# 8eye_line_sensor.net
KiCad netlist of a schematic drawn in EAGLE
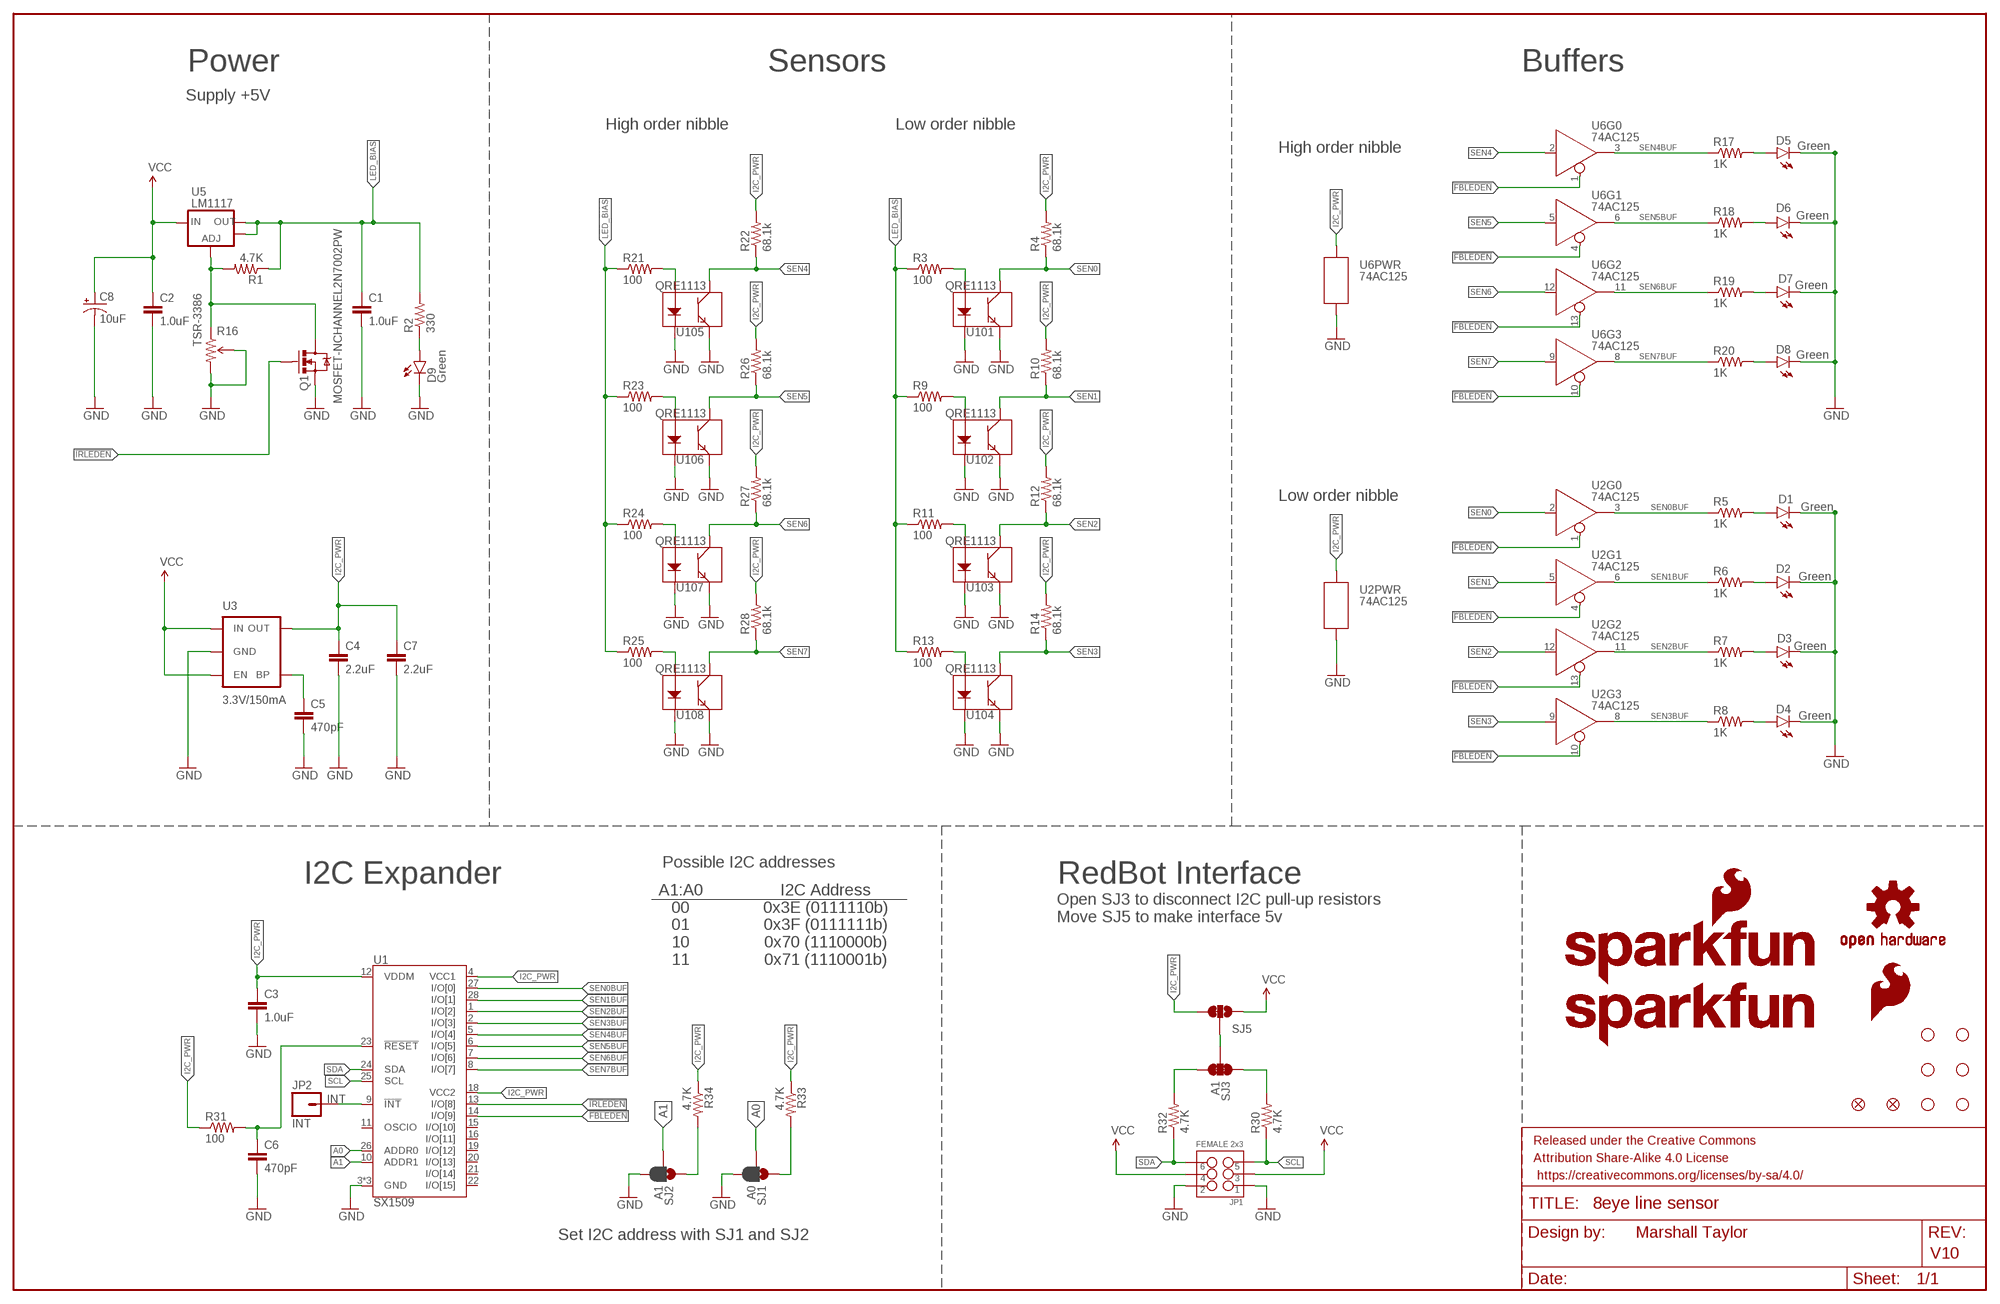
[diagram p0: schematic, sheet 1]

(export (version "E")
  (design (tool "Eeschema 10.0.6"))
  (components
    (comp (ref "C1")
      (value "1.0uF")
      (footprint "eagle-import:0603-CAP")
      (libsource (lib "eagle-import") (part "1.0UF-16V-10%(0603)"))
    )
    (comp (ref "C2")
      (value "1.0uF")
      (footprint "eagle-import:0603-CAP")
      (libsource (lib "eagle-import") (part "1.0UF-16V-10%(0603)"))
    )
    (comp (ref "C3")
      (value "1.0uF")
      (footprint "eagle-import:0603-CAP")
      (libsource (lib "eagle-import") (part "1.0UF-16V-10%(0603)"))
    )
    (comp (ref "C4")
      (value "2.2uF")
      (footprint "eagle-import:0603-CAP")
      (libsource (lib "eagle-import") (part "2.2UF-10V-20%(0603)"))
    )
    (comp (ref "C5")
      (value "470pF")
      (footprint "eagle-import:0603-CAP")
      (libsource (lib "eagle-import") (part "470PF-50V-5%(0603)SMD"))
    )
    (comp (ref "C6")
      (value "470pF")
      (footprint "eagle-import:0603-CAP")
      (libsource (lib "eagle-import") (part "470PF-50V-5%(0603)SMD"))
    )
    (comp (ref "C7")
      (value "2.2uF")
      (footprint "eagle-import:0603-CAP")
      (libsource (lib "eagle-import") (part "2.2UF-10V-20%(0603)"))
    )
    (comp (ref "C8")
      (value "10uF")
      (footprint "eagle-import:EIA3216")
      (libsource (lib "eagle-import") (part "10UF-16V-10%(TANT)"))
    )
    (comp (ref "D1")
      (value "Green")
      (footprint "eagle-import:LED-1206-BOTTOM")
      (libsource (lib "eagle-import") (part "LED-GREEN1206-BOTTOM"))
    )
    (comp (ref "D2")
      (value "Green")
      (footprint "eagle-import:LED-1206-BOTTOM")
      (libsource (lib "eagle-import") (part "LED-GREEN1206-BOTTOM"))
    )
    (comp (ref "D3")
      (value "Green")
      (footprint "eagle-import:LED-1206-BOTTOM")
      (libsource (lib "eagle-import") (part "LED-GREEN1206-BOTTOM"))
    )
    (comp (ref "D4")
      (value "Green")
      (footprint "eagle-import:LED-1206-BOTTOM")
      (libsource (lib "eagle-import") (part "LED-GREEN1206-BOTTOM"))
    )
    (comp (ref "D5")
      (value "Green")
      (footprint "eagle-import:LED-1206-BOTTOM")
      (libsource (lib "eagle-import") (part "LED-GREEN1206-BOTTOM"))
    )
    (comp (ref "D6")
      (value "Green")
      (footprint "eagle-import:LED-1206-BOTTOM")
      (libsource (lib "eagle-import") (part "LED-GREEN1206-BOTTOM"))
    )
    (comp (ref "D7")
      (value "Green")
      (footprint "eagle-import:LED-1206-BOTTOM")
      (libsource (lib "eagle-import") (part "LED-GREEN1206-BOTTOM"))
    )
    (comp (ref "D8")
      (value "Green")
      (footprint "eagle-import:LED-1206-BOTTOM")
      (libsource (lib "eagle-import") (part "LED-GREEN1206-BOTTOM"))
    )
    (comp (ref "D9")
      (value "Green")
      (footprint "eagle-import:LED-1206-BOTTOM")
      (libsource (lib "eagle-import") (part "LED-GREEN1206-BOTTOM"))
    )
    (comp (ref "FID1")
      (value "FIDUCIALUFIDUCIAL")
      (footprint "eagle-import:MICRO-FIDUCIAL")
      (libsource (lib "eagle-import") (part "FIDUCIALUFIDUCIAL"))
    )
    (comp (ref "FID2")
      (value "FIDUCIALUFIDUCIAL")
      (footprint "eagle-import:MICRO-FIDUCIAL")
      (libsource (lib "eagle-import") (part "FIDUCIALUFIDUCIAL"))
    )
    (comp (ref "FRAME2")
      (value "FRAME-LEDGER")
      (footprint "eagle-import:CREATIVE_COMMONS")
      (libsource (lib "eagle-import") (part "FRAME-LEDGER"))
    )
    (comp (ref "JP1")
      (value "FEMALE 2x3")
      (footprint "eagle-import:2X3")
      (libsource (lib "eagle-import") (part "M03X2FEMALE"))
    )
    (comp (ref "JP2")
      (value "INT")
      (footprint "eagle-import:1X01")
      (libsource (lib "eagle-import") (part "M01PTH"))
    )
    (comp (ref "LOGO1")
      (value "SFE_LOGO_NAME_FLAME.2_INCH")
      (footprint "eagle-import:SFE_LOGO_NAME_FLAME_.2")
      (libsource (lib "eagle-import") (part "SFE_LOGO_NAME_FLAME.2_INCH"))
    )
    (comp (ref "LOGO2")
      (value "SFE_LOGO_NAME.2_INCH")
      (footprint "eagle-import:SFE_LOGO_NAME_.2")
      (libsource (lib "eagle-import") (part "SFE_LOGO_NAME.2_INCH"))
    )
    (comp (ref "LOGO5")
      (value "SFE_LOGO_FLAME.3_INCH")
      (footprint "eagle-import:SFE_LOGO_FLAME_.3")
      (libsource (lib "eagle-import") (part "SFE_LOGO_FLAME.3_INCH"))
    )
    (comp (ref "LOGO6")
      (value "OSHW-LOGOS")
      (footprint "eagle-import:OSHW-LOGO-S")
      (libsource (lib "eagle-import") (part "OSHW-LOGOS"))
    )
    (comp (ref "Q1")
      (value "MOSFET-NCHANNEL2N7002PW")
      (footprint "eagle-import:SOT323")
      (libsource (lib "eagle-import") (part "MOSFET-NCHANNEL2N7002PW"))
    )
    (comp (ref "R1")
      (value "4.7K")
      (footprint "eagle-import:0603-RES")
      (libsource (lib "eagle-import") (part "4.7KOHM-1/10W-1%(0603)"))
    )
    (comp (ref "R2")
      (value "330")
      (footprint "eagle-import:0603-RES")
      (libsource (lib "eagle-import") (part "330OHM1/10W1%(0603)"))
    )
    (comp (ref "R3")
      (value "100")
      (footprint "eagle-import:0603-RES")
      (libsource (lib "eagle-import") (part "100OHM-1/10W-1%(0603)"))
    )
    (comp (ref "R4")
      (value "68.1k")
      (footprint "eagle-import:0603-RES")
      (libsource (lib "eagle-import") (part "68.1KOHM1/10W1%(0603)"))
    )
    (comp (ref "R5")
      (value "1K")
      (footprint "eagle-import:0603-RES")
      (libsource (lib "eagle-import") (part "1KOHM-1/10W-1%(0603)"))
    )
    (comp (ref "R6")
      (value "1K")
      (footprint "eagle-import:0603-RES")
      (libsource (lib "eagle-import") (part "1KOHM-1/10W-1%(0603)"))
    )
    (comp (ref "R7")
      (value "1K")
      (footprint "eagle-import:0603-RES")
      (libsource (lib "eagle-import") (part "1KOHM-1/10W-1%(0603)"))
    )
    (comp (ref "R8")
      (value "1K")
      (footprint "eagle-import:0603-RES")
      (libsource (lib "eagle-import") (part "1KOHM-1/10W-1%(0603)"))
    )
    (comp (ref "R9")
      (value "100")
      (footprint "eagle-import:0603-RES")
      (libsource (lib "eagle-import") (part "100OHM-1/10W-1%(0603)"))
    )
    (comp (ref "R10")
      (value "68.1k")
      (footprint "eagle-import:0603-RES")
      (libsource (lib "eagle-import") (part "68.1KOHM1/10W1%(0603)"))
    )
    (comp (ref "R11")
      (value "100")
      (footprint "eagle-import:0603-RES")
      (libsource (lib "eagle-import") (part "100OHM-1/10W-1%(0603)"))
    )
    (comp (ref "R12")
      (value "68.1k")
      (footprint "eagle-import:0603-RES")
      (libsource (lib "eagle-import") (part "68.1KOHM1/10W1%(0603)"))
    )
    (comp (ref "R13")
      (value "100")
      (footprint "eagle-import:0603-RES")
      (libsource (lib "eagle-import") (part "100OHM-1/10W-1%(0603)"))
    )
    (comp (ref "R14")
      (value "68.1k")
      (footprint "eagle-import:0603-RES")
      (libsource (lib "eagle-import") (part "68.1KOHM1/10W1%(0603)"))
    )
    (comp (ref "R16")
      (value "TSR-3386")
      (footprint "eagle-import:3386U")
      (libsource (lib "eagle-import") (part "TRIMPOT-PTH-KNOB"))
    )
    (comp (ref "R17")
      (value "1K")
      (footprint "eagle-import:0603-RES")
      (libsource (lib "eagle-import") (part "1KOHM-1/10W-1%(0603)"))
    )
    (comp (ref "R18")
      (value "1K")
      (footprint "eagle-import:0603-RES")
      (libsource (lib "eagle-import") (part "1KOHM-1/10W-1%(0603)"))
    )
    (comp (ref "R19")
      (value "1K")
      (footprint "eagle-import:0603-RES")
      (libsource (lib "eagle-import") (part "1KOHM-1/10W-1%(0603)"))
    )
    (comp (ref "R20")
      (value "1K")
      (footprint "eagle-import:0603-RES")
      (libsource (lib "eagle-import") (part "1KOHM-1/10W-1%(0603)"))
    )
    (comp (ref "R21")
      (value "100")
      (footprint "eagle-import:0603-RES")
      (libsource (lib "eagle-import") (part "100OHM-1/10W-1%(0603)"))
    )
    (comp (ref "R22")
      (value "68.1k")
      (footprint "eagle-import:0603-RES")
      (libsource (lib "eagle-import") (part "68.1KOHM1/10W1%(0603)"))
    )
    (comp (ref "R23")
      (value "100")
      (footprint "eagle-import:0603-RES")
      (libsource (lib "eagle-import") (part "100OHM-1/10W-1%(0603)"))
    )
    (comp (ref "R24")
      (value "100")
      (footprint "eagle-import:0603-RES")
      (libsource (lib "eagle-import") (part "100OHM-1/10W-1%(0603)"))
    )
    (comp (ref "R25")
      (value "100")
      (footprint "eagle-import:0603-RES")
      (libsource (lib "eagle-import") (part "100OHM-1/10W-1%(0603)"))
    )
    (comp (ref "R26")
      (value "68.1k")
      (footprint "eagle-import:0603-RES")
      (libsource (lib "eagle-import") (part "68.1KOHM1/10W1%(0603)"))
    )
    (comp (ref "R27")
      (value "68.1k")
      (footprint "eagle-import:0603-RES")
      (libsource (lib "eagle-import") (part "68.1KOHM1/10W1%(0603)"))
    )
    (comp (ref "R28")
      (value "68.1k")
      (footprint "eagle-import:0603-RES")
      (libsource (lib "eagle-import") (part "68.1KOHM1/10W1%(0603)"))
    )
    (comp (ref "R30")
      (value "4.7K")
      (footprint "eagle-import:0603-RES")
      (libsource (lib "eagle-import") (part "4.7KOHM-1/10W-1%(0603)"))
    )
    (comp (ref "R31")
      (value "100")
      (footprint "eagle-import:0603-RES")
      (libsource (lib "eagle-import") (part "100OHM-1/10W-1%(0603)"))
    )
    (comp (ref "R32")
      (value "4.7K")
      (footprint "eagle-import:0603-RES")
      (libsource (lib "eagle-import") (part "4.7KOHM-1/10W-1%(0603)"))
    )
    (comp (ref "R33")
      (value "4.7K")
      (footprint "eagle-import:0603-RES")
      (libsource (lib "eagle-import") (part "4.7KOHM-1/10W-1%(0603)"))
    )
    (comp (ref "R34")
      (value "4.7K")
      (footprint "eagle-import:0603-RES")
      (libsource (lib "eagle-import") (part "4.7KOHM-1/10W-1%(0603)"))
    )
    (comp (ref "SJ1")
      (value "A0")
      (footprint "eagle-import:PAD-JUMPER-3-2OF3_NC_BY_PASTE_YES_SILK_FULL_BOX")
      (libsource (lib "eagle-import") (part "JUMPER-PAD-3-2OF3_NC_BY_PASTE"))
    )
    (comp (ref "SJ2")
      (value "A1")
      (footprint "eagle-import:PAD-JUMPER-3-2OF3_NC_BY_PASTE_YES_SILK_FULL_BOX")
      (libsource (lib "eagle-import") (part "JUMPER-PAD-3-2OF3_NC_BY_PASTE"))
    )
    (comp (ref "SJ3")
      (value "A1")
      (footprint "eagle-import:PAD-JUMPER-3-3OF3_NC_BY_TRACE_YES_SILK_FULL_BOX")
      (libsource (lib "eagle-import") (part "JUMPER-PAD-3-NC_BY_TRACE"))
    )
    (comp (ref "SJ5")
      (value "JUMPER-PAD-3-2OF3_NC_BY_TRACE_SMALL")
      (footprint "eagle-import:PAD-JUMPER-3-2OF3_NC_BY_TRACE_YES_SILK_FULL_BOX")
      (libsource (lib "eagle-import") (part "JUMPER-PAD-3-2OF3_NC_BY_TRACE_SMALL"))
    )
    (comp (ref "STANDOFF1")
      (value "STAND-OFF")
      (footprint "eagle-import:STAND-OFF")
      (libsource (lib "eagle-import") (part "STAND-OFF"))
    )
    (comp (ref "STANDOFF2")
      (value "STAND-OFF")
      (footprint "eagle-import:STAND-OFF")
      (libsource (lib "eagle-import") (part "STAND-OFF"))
    )
    (comp (ref "STANDOFF3")
      (value "STAND-OFF")
      (footprint "eagle-import:STAND-OFF")
      (libsource (lib "eagle-import") (part "STAND-OFF"))
    )
    (comp (ref "STANDOFF4")
      (value "STAND-OFF")
      (footprint "eagle-import:STAND-OFF")
      (libsource (lib "eagle-import") (part "STAND-OFF"))
    )
    (comp (ref "STANDOFF5")
      (value "STAND-OFF")
      (footprint "eagle-import:STAND-OFF")
      (libsource (lib "eagle-import") (part "STAND-OFF"))
    )
    (comp (ref "STANDOFF6")
      (value "STAND-OFF")
      (footprint "eagle-import:STAND-OFF")
      (libsource (lib "eagle-import") (part "STAND-OFF"))
    )
    (comp (ref "U1")
      (value "SX1509")
      (footprint "eagle-import:QFN-28")
      (libsource (lib "eagle-import") (part "SX1509"))
    )
    (comp (ref "U2")
      (value "74AC125")
      (footprint "eagle-import:SO14")
      (libsource (lib "eagle-import") (part "74125AC125DG"))
    )
    (comp (ref "U3")
      (value "3.3V/150mA")
      (footprint "eagle-import:SOT23-5")
      (libsource (lib "eagle-import") (part "V_REG_MIC52053.3V"))
    )
    (comp (ref "U5")
      (value "LM1117")
      (footprint "eagle-import:SOT223")
      (libsource (lib "eagle-import") (part "V_REG_LM1117SOT223"))
    )
    (comp (ref "U6")
      (value "74AC125")
      (footprint "eagle-import:SO14")
      (libsource (lib "eagle-import") (part "74125AC125DG"))
    )
    (comp (ref "U101")
      (value "QRE1113")
      (footprint "eagle-import:QRE1113")
      (libsource (lib "eagle-import") (part "QRE1113"))
    )
    (comp (ref "U102")
      (value "QRE1113")
      (footprint "eagle-import:QRE1113")
      (libsource (lib "eagle-import") (part "QRE1113"))
    )
    (comp (ref "U103")
      (value "QRE1113")
      (footprint "eagle-import:QRE1113")
      (libsource (lib "eagle-import") (part "QRE1113"))
    )
    (comp (ref "U104")
      (value "QRE1113")
      (footprint "eagle-import:QRE1113")
      (libsource (lib "eagle-import") (part "QRE1113"))
    )
    (comp (ref "U105")
      (value "QRE1113")
      (footprint "eagle-import:QRE1113")
      (libsource (lib "eagle-import") (part "QRE1113"))
    )
    (comp (ref "U106")
      (value "QRE1113")
      (footprint "eagle-import:QRE1113")
      (libsource (lib "eagle-import") (part "QRE1113"))
    )
    (comp (ref "U107")
      (value "QRE1113")
      (footprint "eagle-import:QRE1113")
      (libsource (lib "eagle-import") (part "QRE1113"))
    )
    (comp (ref "U108")
      (value "QRE1113")
      (footprint "eagle-import:QRE1113")
      (libsource (lib "eagle-import") (part "QRE1113"))
    )
  )
  (nets
    (net (code "1") (name "/INT") (class "Default")
      (node (ref "JP2") (pin "1") (pinfunction "1_1") (pintype "passive"))
      (node (ref "U1") (pin "9") (pinfunction "~{INT}_9") (pintype "bidirectional"))
    )
    (net (code "2") (name "/~{FBLEDEN}") (class "Default")
      (node (ref "U1") (pin "14") (pinfunction "I/O[9]_14") (pintype "bidirectional"))
      (node (ref "U2") (pin "1") (pinfunction "~{EN}_1") (pintype "bidirectional"))
      (node (ref "U2") (pin "10") (pinfunction "~{EN}_10") (pintype "bidirectional"))
      (node (ref "U2") (pin "13") (pinfunction "~{EN}_13") (pintype "bidirectional"))
      (node (ref "U2") (pin "4") (pinfunction "~{EN}_4") (pintype "bidirectional"))
      (node (ref "U6") (pin "1") (pinfunction "~{EN}_1") (pintype "bidirectional"))
      (node (ref "U6") (pin "10") (pinfunction "~{EN}_10") (pintype "bidirectional"))
      (node (ref "U6") (pin "13") (pinfunction "~{EN}_13") (pintype "bidirectional"))
      (node (ref "U6") (pin "4") (pinfunction "~{EN}_4") (pintype "bidirectional"))
    )
    (net (code "3") (name "/~{IRLEDEN}") (class "Default")
      (node (ref "Q1") (pin "1") (pinfunction "G_1") (pintype "passive"))
      (node (ref "U1") (pin "13") (pinfunction "I/O[8]_13") (pintype "bidirectional"))
    )
    (net (code "4") (name "A0") (class "Default")
      (node (ref "SJ1") (pin "2") (pinfunction "2_2") (pintype "passive"))
      (node (ref "U1") (pin "26") (pinfunction "ADDR0_26") (pintype "bidirectional"))
    )
    (net (code "5") (name "A1") (class "Default")
      (node (ref "SJ2") (pin "2") (pinfunction "2_2") (pintype "passive"))
      (node (ref "U1") (pin "10") (pinfunction "ADDR1_10") (pintype "bidirectional"))
    )
    (net (code "6") (name "GND") (class "Default")
      (node (ref "C1") (pin "2") (pinfunction "2_2") (pintype "passive"))
      (node (ref "C2") (pin "2") (pinfunction "2_2") (pintype "passive"))
      (node (ref "C3") (pin "2") (pinfunction "2_2") (pintype "passive"))
      (node (ref "C4") (pin "2") (pinfunction "2_2") (pintype "passive"))
      (node (ref "C5") (pin "2") (pinfunction "2_2") (pintype "passive"))
      (node (ref "C6") (pin "2") (pinfunction "2_2") (pintype "passive"))
      (node (ref "C7") (pin "2") (pinfunction "2_2") (pintype "passive"))
      (node (ref "C8") (pin "C") (pinfunction "-_C") (pintype "passive"))
      (node (ref "D1") (pin "C") (pinfunction "C_C") (pintype "passive"))
      (node (ref "D2") (pin "C") (pinfunction "C_C") (pintype "passive"))
      (node (ref "D3") (pin "C") (pinfunction "C_C") (pintype "passive"))
      (node (ref "D4") (pin "C") (pinfunction "C_C") (pintype "passive"))
      (node (ref "D5") (pin "C") (pinfunction "C_C") (pintype "passive"))
      (node (ref "D6") (pin "C") (pinfunction "C_C") (pintype "passive"))
      (node (ref "D7") (pin "C") (pinfunction "C_C") (pintype "passive"))
      (node (ref "D8") (pin "C") (pinfunction "C_C") (pintype "passive"))
      (node (ref "D9") (pin "C") (pinfunction "C_C") (pintype "passive"))
      (node (ref "JP1") (pin "1") (pinfunction "1_1") (pintype "bidirectional"))
      (node (ref "JP1") (pin "2") (pinfunction "2_2") (pintype "bidirectional"))
      (node (ref "Q1") (pin "2") (pinfunction "S_2") (pintype "passive"))
      (node (ref "R16") (pin "2") (pinfunction "WIPER_2") (pintype "passive"))
      (node (ref "R16") (pin "3") (pinfunction "CW_3") (pintype "passive"))
      (node (ref "SJ1") (pin "3") (pinfunction "3_3") (pintype "passive"))
      (node (ref "SJ2") (pin "3") (pinfunction "3_3") (pintype "passive"))
      (node (ref "U1") (pin "17") (pinfunction "GND_17") (pintype "bidirectional"))
      (node (ref "U1") (pin "29") (pinfunction "GND_29") (pintype "bidirectional"))
      (node (ref "U1") (pin "3") (pinfunction "GND_3") (pintype "bidirectional"))
      (node (ref "U101") (pin "2") (pinfunction "K_2") (pintype "bidirectional"))
      (node (ref "U101") (pin "4") (pinfunction "E_4") (pintype "bidirectional"))
      (node (ref "U102") (pin "2") (pinfunction "K_2") (pintype "bidirectional"))
      (node (ref "U102") (pin "4") (pinfunction "E_4") (pintype "bidirectional"))
      (node (ref "U103") (pin "2") (pinfunction "K_2") (pintype "bidirectional"))
      (node (ref "U103") (pin "4") (pinfunction "E_4") (pintype "bidirectional"))
      (node (ref "U104") (pin "2") (pinfunction "K_2") (pintype "bidirectional"))
      (node (ref "U104") (pin "4") (pinfunction "E_4") (pintype "bidirectional"))
      (node (ref "U105") (pin "2") (pinfunction "K_2") (pintype "bidirectional"))
      (node (ref "U105") (pin "4") (pinfunction "E_4") (pintype "bidirectional"))
      (node (ref "U106") (pin "2") (pinfunction "K_2") (pintype "bidirectional"))
      (node (ref "U106") (pin "4") (pinfunction "E_4") (pintype "bidirectional"))
      (node (ref "U107") (pin "2") (pinfunction "K_2") (pintype "bidirectional"))
      (node (ref "U107") (pin "4") (pinfunction "E_4") (pintype "bidirectional"))
      (node (ref "U108") (pin "2") (pinfunction "K_2") (pintype "bidirectional"))
      (node (ref "U108") (pin "4") (pinfunction "E_4") (pintype "bidirectional"))
      (node (ref "U2") (pin "7") (pinfunction "P$V-_7") (pintype "bidirectional"))
      (node (ref "U3") (pin "2") (pinfunction "GND_2") (pintype "input"))
      (node (ref "U6") (pin "7") (pinfunction "P$V-_7") (pintype "bidirectional"))
    )
    (net (code "7") (name "I2C_PWR") (class "Default")
      (node (ref "C3") (pin "1") (pinfunction "1_1") (pintype "passive"))
      (node (ref "C4") (pin "1") (pinfunction "1_1") (pintype "passive"))
      (node (ref "C7") (pin "1") (pinfunction "1_1") (pintype "passive"))
      (node (ref "R10") (pin "2") (pinfunction "2_2") (pintype "passive"))
      (node (ref "R12") (pin "2") (pinfunction "2_2") (pintype "passive"))
      (node (ref "R14") (pin "2") (pinfunction "2_2") (pintype "passive"))
      (node (ref "R22") (pin "2") (pinfunction "2_2") (pintype "passive"))
      (node (ref "R26") (pin "2") (pinfunction "2_2") (pintype "passive"))
      (node (ref "R27") (pin "2") (pinfunction "2_2") (pintype "passive"))
      (node (ref "R28") (pin "2") (pinfunction "2_2") (pintype "passive"))
      (node (ref "R31") (pin "1") (pinfunction "1_1") (pintype "passive"))
      (node (ref "R33") (pin "1") (pinfunction "1_1") (pintype "passive"))
      (node (ref "R34") (pin "1") (pinfunction "1_1") (pintype "passive"))
      (node (ref "R4") (pin "2") (pinfunction "2_2") (pintype "passive"))
      (node (ref "SJ5") (pin "3") (pinfunction "3_3") (pintype "passive"))
      (node (ref "U1") (pin "12") (pinfunction "VDDM_12") (pintype "bidirectional"))
      (node (ref "U1") (pin "18") (pinfunction "VCC2_18") (pintype "bidirectional"))
      (node (ref "U1") (pin "4") (pinfunction "VCC1_4") (pintype "bidirectional"))
      (node (ref "U2") (pin "14") (pinfunction "P$V+_14") (pintype "bidirectional"))
      (node (ref "U3") (pin "5") (pinfunction "OUT_5") (pintype "passive"))
      (node (ref "U6") (pin "14") (pinfunction "P$V+_14") (pintype "bidirectional"))
    )
    (net (code "8") (name "LED_BIAS") (class "Default")
      (node (ref "C1") (pin "1") (pinfunction "1_1") (pintype "passive"))
      (node (ref "R1") (pin "1") (pinfunction "1_1") (pintype "passive"))
      (node (ref "R11") (pin "1") (pinfunction "1_1") (pintype "passive"))
      (node (ref "R13") (pin "1") (pinfunction "1_1") (pintype "passive"))
      (node (ref "R2") (pin "2") (pinfunction "2_2") (pintype "passive"))
      (node (ref "R21") (pin "1") (pinfunction "1_1") (pintype "passive"))
      (node (ref "R23") (pin "1") (pinfunction "1_1") (pintype "passive"))
      (node (ref "R24") (pin "1") (pinfunction "1_1") (pintype "passive"))
      (node (ref "R25") (pin "1") (pinfunction "1_1") (pintype "passive"))
      (node (ref "R3") (pin "1") (pinfunction "1_1") (pintype "passive"))
      (node (ref "R9") (pin "1") (pinfunction "1_1") (pintype "passive"))
      (node (ref "U5") (pin "2") (pinfunction "OUT_2") (pintype "output"))
      (node (ref "U5") (pin "4") (pinfunction "OUT_4") (pintype "output"))
    )
    (net (code "9") (name "Net-(D1-PadA)") (class "Default")
      (node (ref "D1") (pin "A") (pinfunction "A_A") (pintype "passive"))
      (node (ref "R5") (pin "2") (pinfunction "2_2") (pintype "passive"))
    )
    (net (code "10") (name "Net-(D2-PadA)") (class "Default")
      (node (ref "D2") (pin "A") (pinfunction "A_A") (pintype "passive"))
      (node (ref "R6") (pin "2") (pinfunction "2_2") (pintype "passive"))
    )
    (net (code "11") (name "Net-(D3-PadA)") (class "Default")
      (node (ref "D3") (pin "A") (pinfunction "A_A") (pintype "passive"))
      (node (ref "R7") (pin "2") (pinfunction "2_2") (pintype "passive"))
    )
    (net (code "12") (name "Net-(D4-PadA)") (class "Default")
      (node (ref "D4") (pin "A") (pinfunction "A_A") (pintype "passive"))
      (node (ref "R8") (pin "2") (pinfunction "2_2") (pintype "passive"))
    )
    (net (code "13") (name "Net-(D5-PadA)") (class "Default")
      (node (ref "D5") (pin "A") (pinfunction "A_A") (pintype "passive"))
      (node (ref "R17") (pin "2") (pinfunction "2_2") (pintype "passive"))
    )
    (net (code "14") (name "Net-(D6-PadA)") (class "Default")
      (node (ref "D6") (pin "A") (pinfunction "A_A") (pintype "passive"))
      (node (ref "R18") (pin "2") (pinfunction "2_2") (pintype "passive"))
    )
    (net (code "15") (name "Net-(D7-PadA)") (class "Default")
      (node (ref "D7") (pin "A") (pinfunction "A_A") (pintype "passive"))
      (node (ref "R19") (pin "2") (pinfunction "2_2") (pintype "passive"))
    )
    (net (code "16") (name "Net-(D8-PadA)") (class "Default")
      (node (ref "D8") (pin "A") (pinfunction "A_A") (pintype "passive"))
      (node (ref "R20") (pin "2") (pinfunction "2_2") (pintype "passive"))
    )
    (net (code "17") (name "Net-(D9-PadA)") (class "Default")
      (node (ref "D9") (pin "A") (pinfunction "A_A") (pintype "passive"))
      (node (ref "R2") (pin "1") (pinfunction "1_1") (pintype "passive"))
    )
    (net (code "18") (name "Net-(Q1-D)") (class "Default")
      (node (ref "Q1") (pin "3") (pinfunction "D_3") (pintype "passive"))
      (node (ref "R1") (pin "2") (pinfunction "2_2") (pintype "passive"))
      (node (ref "R16") (pin "1") (pinfunction "CCW_1") (pintype "passive"))
      (node (ref "U5") (pin "1") (pinfunction "ADJ_1") (pintype "input"))
    )
    (net (code "19") (name "Net-(R30-Pad2)") (class "Default")
      (node (ref "R30") (pin "2") (pinfunction "2_2") (pintype "passive"))
      (node (ref "SJ3") (pin "1") (pinfunction "1_1") (pintype "passive"))
    )
    (net (code "20") (name "Net-(R32-Pad2)") (class "Default")
      (node (ref "R32") (pin "2") (pinfunction "2_2") (pintype "passive"))
      (node (ref "SJ3") (pin "3") (pinfunction "3_3") (pintype "passive"))
    )
    (net (code "21") (name "Net-(R33-Pad2)") (class "Default")
      (node (ref "R33") (pin "2") (pinfunction "2_2") (pintype "passive"))
      (node (ref "SJ1") (pin "1") (pinfunction "1_1") (pintype "passive"))
    )
    (net (code "22") (name "Net-(R34-Pad2)") (class "Default")
      (node (ref "R34") (pin "2") (pinfunction "2_2") (pintype "passive"))
      (node (ref "SJ2") (pin "1") (pinfunction "1_1") (pintype "passive"))
    )
    (net (code "23") (name "Net-(SJ3-Pad2)") (class "Default")
      (node (ref "SJ3") (pin "2") (pinfunction "2_2") (pintype "passive"))
      (node (ref "SJ5") (pin "2") (pinfunction "2_2") (pintype "passive"))
    )
    (net (code "24") (name "Net-(U1-~{RESET})") (class "Default")
      (node (ref "C6") (pin "1") (pinfunction "1_1") (pintype "passive"))
      (node (ref "R31") (pin "2") (pinfunction "2_2") (pintype "passive"))
      (node (ref "U1") (pin "23") (pinfunction "~{RESET}_23") (pintype "bidirectional"))
    )
    (net (code "25") (name "Net-(U3-BP)") (class "Default")
      (node (ref "C5") (pin "1") (pinfunction "1_1") (pintype "passive"))
      (node (ref "U3") (pin "4") (pinfunction "BP_4") (pintype "input"))
    )
    (net (code "26") (name "Net-(U101-A)") (class "Default")
      (node (ref "R3") (pin "2") (pinfunction "2_2") (pintype "passive"))
      (node (ref "U101") (pin "1") (pinfunction "A_1") (pintype "bidirectional"))
    )
    (net (code "27") (name "Net-(U102-A)") (class "Default")
      (node (ref "R9") (pin "2") (pinfunction "2_2") (pintype "passive"))
      (node (ref "U102") (pin "1") (pinfunction "A_1") (pintype "bidirectional"))
    )
    (net (code "28") (name "Net-(U103-A)") (class "Default")
      (node (ref "R11") (pin "2") (pinfunction "2_2") (pintype "passive"))
      (node (ref "U103") (pin "1") (pinfunction "A_1") (pintype "bidirectional"))
    )
    (net (code "29") (name "Net-(U104-A)") (class "Default")
      (node (ref "R13") (pin "2") (pinfunction "2_2") (pintype "passive"))
      (node (ref "U104") (pin "1") (pinfunction "A_1") (pintype "bidirectional"))
    )
    (net (code "30") (name "Net-(U105-A)") (class "Default")
      (node (ref "R21") (pin "2") (pinfunction "2_2") (pintype "passive"))
      (node (ref "U105") (pin "1") (pinfunction "A_1") (pintype "bidirectional"))
    )
    (net (code "31") (name "Net-(U106-A)") (class "Default")
      (node (ref "R23") (pin "2") (pinfunction "2_2") (pintype "passive"))
      (node (ref "U106") (pin "1") (pinfunction "A_1") (pintype "bidirectional"))
    )
    (net (code "32") (name "Net-(U107-A)") (class "Default")
      (node (ref "R24") (pin "2") (pinfunction "2_2") (pintype "passive"))
      (node (ref "U107") (pin "1") (pinfunction "A_1") (pintype "bidirectional"))
    )
    (net (code "33") (name "Net-(U108-A)") (class "Default")
      (node (ref "R25") (pin "2") (pinfunction "2_2") (pintype "passive"))
      (node (ref "U108") (pin "1") (pinfunction "A_1") (pintype "bidirectional"))
    )
    (net (code "34") (name "SCL") (class "Default")
      (node (ref "JP1") (pin "5") (pinfunction "5_5") (pintype "bidirectional"))
      (node (ref "R30") (pin "1") (pinfunction "1_1") (pintype "passive"))
      (node (ref "U1") (pin "25") (pinfunction "SCL_25") (pintype "bidirectional"))
    )
    (net (code "35") (name "SDA") (class "Default")
      (node (ref "JP1") (pin "6") (pinfunction "6_6") (pintype "bidirectional"))
      (node (ref "R32") (pin "1") (pinfunction "1_1") (pintype "passive"))
      (node (ref "U1") (pin "24") (pinfunction "SDA_24") (pintype "bidirectional"))
    )
    (net (code "36") (name "SEN0") (class "Default")
      (node (ref "R4") (pin "1") (pinfunction "1_1") (pintype "passive"))
      (node (ref "U101") (pin "3") (pinfunction "C_3") (pintype "bidirectional"))
      (node (ref "U2") (pin "2") (pinfunction "D_2") (pintype "bidirectional"))
    )
    (net (code "37") (name "SEN0BUF") (class "Default")
      (node (ref "R5") (pin "1") (pinfunction "1_1") (pintype "passive"))
      (node (ref "U1") (pin "27") (pinfunction "I/O[0]_27") (pintype "bidirectional"))
      (node (ref "U2") (pin "3") (pinfunction "Q_3") (pintype "bidirectional"))
    )
    (net (code "38") (name "SEN1") (class "Default")
      (node (ref "R10") (pin "1") (pinfunction "1_1") (pintype "passive"))
      (node (ref "U102") (pin "3") (pinfunction "C_3") (pintype "bidirectional"))
      (node (ref "U2") (pin "5") (pinfunction "D_5") (pintype "bidirectional"))
    )
    (net (code "39") (name "SEN1BUF") (class "Default")
      (node (ref "R6") (pin "1") (pinfunction "1_1") (pintype "passive"))
      (node (ref "U1") (pin "28") (pinfunction "I/O[1]_28") (pintype "bidirectional"))
      (node (ref "U2") (pin "6") (pinfunction "Q_6") (pintype "bidirectional"))
    )
    (net (code "40") (name "SEN2") (class "Default")
      (node (ref "R12") (pin "1") (pinfunction "1_1") (pintype "passive"))
      (node (ref "U103") (pin "3") (pinfunction "C_3") (pintype "bidirectional"))
      (node (ref "U2") (pin "12") (pinfunction "D_12") (pintype "bidirectional"))
    )
    (net (code "41") (name "SEN2BUF") (class "Default")
      (node (ref "R7") (pin "1") (pinfunction "1_1") (pintype "passive"))
      (node (ref "U1") (pin "1") (pinfunction "I/O[2]_1") (pintype "bidirectional"))
      (node (ref "U2") (pin "11") (pinfunction "Q_11") (pintype "bidirectional"))
    )
    (net (code "42") (name "SEN3") (class "Default")
      (node (ref "R14") (pin "1") (pinfunction "1_1") (pintype "passive"))
      (node (ref "U104") (pin "3") (pinfunction "C_3") (pintype "bidirectional"))
      (node (ref "U2") (pin "9") (pinfunction "D_9") (pintype "bidirectional"))
    )
    (net (code "43") (name "SEN3BUF") (class "Default")
      (node (ref "R8") (pin "1") (pinfunction "1_1") (pintype "passive"))
      (node (ref "U1") (pin "2") (pinfunction "I/O[3]_2") (pintype "bidirectional"))
      (node (ref "U2") (pin "8") (pinfunction "Q_8") (pintype "bidirectional"))
    )
    (net (code "44") (name "SEN4") (class "Default")
      (node (ref "R22") (pin "1") (pinfunction "1_1") (pintype "passive"))
      (node (ref "U105") (pin "3") (pinfunction "C_3") (pintype "bidirectional"))
      (node (ref "U6") (pin "2") (pinfunction "D_2") (pintype "bidirectional"))
    )
    (net (code "45") (name "SEN4BUF") (class "Default")
      (node (ref "R17") (pin "1") (pinfunction "1_1") (pintype "passive"))
      (node (ref "U1") (pin "5") (pinfunction "I/O[4]_5") (pintype "bidirectional"))
      (node (ref "U6") (pin "3") (pinfunction "Q_3") (pintype "bidirectional"))
    )
    (net (code "46") (name "SEN5") (class "Default")
      (node (ref "R26") (pin "1") (pinfunction "1_1") (pintype "passive"))
      (node (ref "U106") (pin "3") (pinfunction "C_3") (pintype "bidirectional"))
      (node (ref "U6") (pin "5") (pinfunction "D_5") (pintype "bidirectional"))
    )
    (net (code "47") (name "SEN5BUF") (class "Default")
      (node (ref "R18") (pin "1") (pinfunction "1_1") (pintype "passive"))
      (node (ref "U1") (pin "6") (pinfunction "I/O[5]_6") (pintype "bidirectional"))
      (node (ref "U6") (pin "6") (pinfunction "Q_6") (pintype "bidirectional"))
    )
    (net (code "48") (name "SEN6") (class "Default")
      (node (ref "R27") (pin "1") (pinfunction "1_1") (pintype "passive"))
      (node (ref "U107") (pin "3") (pinfunction "C_3") (pintype "bidirectional"))
      (node (ref "U6") (pin "12") (pinfunction "D_12") (pintype "bidirectional"))
    )
    (net (code "49") (name "SEN6BUF") (class "Default")
      (node (ref "R19") (pin "1") (pinfunction "1_1") (pintype "passive"))
      (node (ref "U1") (pin "7") (pinfunction "I/O[6]_7") (pintype "bidirectional"))
      (node (ref "U6") (pin "11") (pinfunction "Q_11") (pintype "bidirectional"))
    )
    (net (code "50") (name "SEN7") (class "Default")
      (node (ref "R28") (pin "1") (pinfunction "1_1") (pintype "passive"))
      (node (ref "U108") (pin "3") (pinfunction "C_3") (pintype "bidirectional"))
      (node (ref "U6") (pin "9") (pinfunction "D_9") (pintype "bidirectional"))
    )
    (net (code "51") (name "SEN7BUF") (class "Default")
      (node (ref "R20") (pin "1") (pinfunction "1_1") (pintype "passive"))
      (node (ref "U1") (pin "8") (pinfunction "I/O[7]_8") (pintype "bidirectional"))
      (node (ref "U6") (pin "8") (pinfunction "Q_8") (pintype "bidirectional"))
    )
    (net (code "52") (name "VCC") (class "Default")
      (node (ref "C2") (pin "1") (pinfunction "1_1") (pintype "passive"))
      (node (ref "C8") (pin "A") (pinfunction "+_A") (pintype "passive"))
      (node (ref "JP1") (pin "3") (pinfunction "3_3") (pintype "bidirectional"))
      (node (ref "JP1") (pin "4") (pinfunction "4_4") (pintype "bidirectional"))
      (node (ref "SJ5") (pin "1") (pinfunction "1_1") (pintype "passive"))
      (node (ref "U3") (pin "1") (pinfunction "IN_1") (pintype "input"))
      (node (ref "U3") (pin "3") (pinfunction "EN_3") (pintype "input"))
      (node (ref "U5") (pin "3") (pinfunction "IN_3") (pintype "input"))
    )
    (net (code "53") (name "unconnected-(U1-I{slash}O[10]-Pad15)") (class "Default")
      (node (ref "U1") (pin "15") (pinfunction "I/O[10]_15") (pintype "bidirectional"))
    )
    (net (code "54") (name "unconnected-(U1-I{slash}O[11]-Pad16)") (class "Default")
      (node (ref "U1") (pin "16") (pinfunction "I/O[11]_16") (pintype "bidirectional"))
    )
    (net (code "55") (name "unconnected-(U1-I{slash}O[12]-Pad19)") (class "Default")
      (node (ref "U1") (pin "19") (pinfunction "I/O[12]_19") (pintype "bidirectional"))
    )
    (net (code "56") (name "unconnected-(U1-I{slash}O[13]-Pad20)") (class "Default")
      (node (ref "U1") (pin "20") (pinfunction "I/O[13]_20") (pintype "bidirectional"))
    )
    (net (code "57") (name "unconnected-(U1-I{slash}O[14]-Pad21)") (class "Default")
      (node (ref "U1") (pin "21") (pinfunction "I/O[14]_21") (pintype "bidirectional"))
    )
    (net (code "58") (name "unconnected-(U1-I{slash}O[15]-Pad22)") (class "Default")
      (node (ref "U1") (pin "22") (pinfunction "I/O[15]_22") (pintype "bidirectional"))
    )
    (net (code "59") (name "unconnected-(U1-OSCIO-Pad11)") (class "Default")
      (node (ref "U1") (pin "11") (pinfunction "OSCIO_11") (pintype "bidirectional"))
    )
  )
)
